# Dashboard_Test_External_rev0.net
KiCad netlist of a schematic drawn in EAGLE
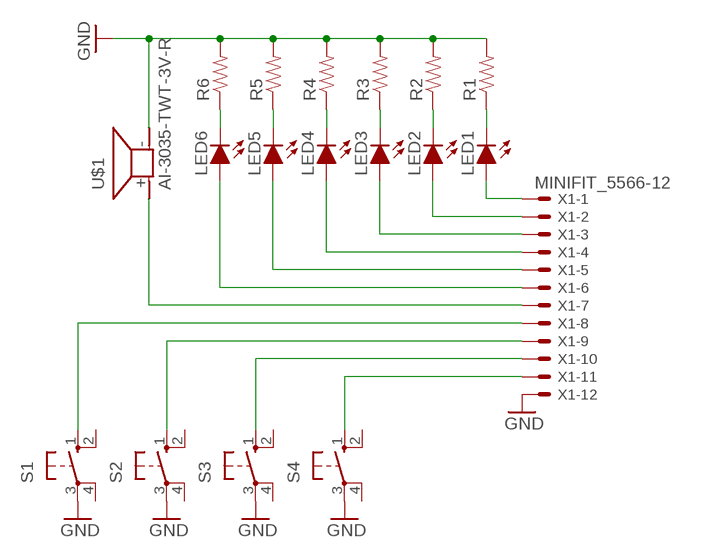
[diagram p0: schematic, sheet 1]

(export (version "E")
  (design (tool "Eeschema 10.0.6"))
  (components
    (comp (ref "LED1")
      (value "LED-5MM")
      (footprint "eagle-import:LED-5MM")
      (libsource (lib "eagle-import") (part "LED-5MM"))
    )
    (comp (ref "LED2")
      (value "LED-5MM")
      (footprint "eagle-import:LED-5MM")
      (libsource (lib "eagle-import") (part "LED-5MM"))
    )
    (comp (ref "LED3")
      (value "LED-5MM")
      (footprint "eagle-import:LED-5MM")
      (libsource (lib "eagle-import") (part "LED-5MM"))
    )
    (comp (ref "LED4")
      (value "LED-5MM")
      (footprint "eagle-import:LED-5MM")
      (libsource (lib "eagle-import") (part "LED-5MM"))
    )
    (comp (ref "LED5")
      (value "LED-5MM")
      (footprint "eagle-import:LED-5MM")
      (libsource (lib "eagle-import") (part "LED-5MM"))
    )
    (comp (ref "LED6")
      (value "LED-5MM")
      (footprint "eagle-import:LED-5MM")
      (libsource (lib "eagle-import") (part "LED-5MM"))
    )
    (comp (ref "R1")
      (value "RESISTOREZ")
      (footprint "eagle-import:AXIAL-0.3EZ")
      (libsource (lib "eagle-import") (part "RESISTOREZ"))
    )
    (comp (ref "R2")
      (value "RESISTOREZ")
      (footprint "eagle-import:AXIAL-0.3EZ")
      (libsource (lib "eagle-import") (part "RESISTOREZ"))
    )
    (comp (ref "R3")
      (value "RESISTOREZ")
      (footprint "eagle-import:AXIAL-0.3EZ")
      (libsource (lib "eagle-import") (part "RESISTOREZ"))
    )
    (comp (ref "R4")
      (value "RESISTOREZ")
      (footprint "eagle-import:AXIAL-0.3EZ")
      (libsource (lib "eagle-import") (part "RESISTOREZ"))
    )
    (comp (ref "R5")
      (value "RESISTOREZ")
      (footprint "eagle-import:AXIAL-0.3EZ")
      (libsource (lib "eagle-import") (part "RESISTOREZ"))
    )
    (comp (ref "R6")
      (value "RESISTOREZ")
      (footprint "eagle-import:AXIAL-0.3EZ")
      (libsource (lib "eagle-import") (part "RESISTOREZ"))
    )
    (comp (ref "S1")
      (value "BTN_10-XX")
      (footprint "eagle-import:B3F-10XX")
      (fields (field (name "MPN") "B3F-1000"))
      (libsource (lib "eagle-import") (part "BTN_10-XX"))
    )
    (comp (ref "S2")
      (value "BTN_10-XX")
      (footprint "eagle-import:B3F-10XX")
      (fields (field (name "MPN") "B3F-1000"))
      (libsource (lib "eagle-import") (part "BTN_10-XX"))
    )
    (comp (ref "S3")
      (value "BTN_10-XX")
      (footprint "eagle-import:B3F-10XX")
      (fields (field (name "MPN") "B3F-1000"))
      (libsource (lib "eagle-import") (part "BTN_10-XX"))
    )
    (comp (ref "S4")
      (value "BTN_10-XX")
      (footprint "eagle-import:B3F-10XX")
      (fields (field (name "MPN") "B3F-1000"))
      (libsource (lib "eagle-import") (part "BTN_10-XX"))
    )
    (comp (ref "U$1")
      (value "AI-3035-TWT-3V-R")
      (footprint "eagle-import:AI-3035-TWT-3V-R")
      (libsource (lib "eagle-import") (part "AI-3035-TWT-3V-R"))
    )
    (comp (ref "X1")
      (value "MINIFIT_5566-12")
      (footprint "eagle-import:MINIFIT_5566-12")
      (libsource (lib "eagle-import") (part "MINIFIT_5566-12"))
    )
  )
  (nets
    (net (code "1") (name "GND") (class "Default")
      (node (ref "R1") (pin "P$2") (pinfunction "2_P$2") (pintype "passive"))
      (node (ref "R2") (pin "P$2") (pinfunction "2_P$2") (pintype "passive"))
      (node (ref "R3") (pin "P$2") (pinfunction "2_P$2") (pintype "passive"))
      (node (ref "R4") (pin "P$2") (pinfunction "2_P$2") (pintype "passive"))
      (node (ref "R5") (pin "P$2") (pinfunction "2_P$2") (pintype "passive"))
      (node (ref "R6") (pin "P$2") (pinfunction "2_P$2") (pintype "passive"))
      (node (ref "S1") (pin "3") (pinfunction "P_3") (pintype "passive"))
      (node (ref "S2") (pin "3") (pinfunction "P_3") (pintype "passive"))
      (node (ref "S3") (pin "3") (pinfunction "P_3") (pintype "passive"))
      (node (ref "S4") (pin "3") (pinfunction "P_3") (pintype "passive"))
      (node (ref "U$1") (pin "P$2") (pinfunction "2_P$2") (pintype "passive"))
      (node (ref "X1") (pin "12") (pinfunction "S_12") (pintype "passive"))
    )
    (net (code "2") (name "Net-(LED1-C)") (class "Default")
      (node (ref "LED1") (pin "K") (pinfunction "C_K") (pintype "passive"))
      (node (ref "R1") (pin "P$1") (pinfunction "1_P$1") (pintype "passive"))
    )
    (net (code "3") (name "Net-(LED2-C)") (class "Default")
      (node (ref "LED2") (pin "K") (pinfunction "C_K") (pintype "passive"))
      (node (ref "R2") (pin "P$1") (pinfunction "1_P$1") (pintype "passive"))
    )
    (net (code "4") (name "Net-(LED3-C)") (class "Default")
      (node (ref "LED3") (pin "K") (pinfunction "C_K") (pintype "passive"))
      (node (ref "R3") (pin "P$1") (pinfunction "1_P$1") (pintype "passive"))
    )
    (net (code "5") (name "Net-(LED4-C)") (class "Default")
      (node (ref "LED4") (pin "K") (pinfunction "C_K") (pintype "passive"))
      (node (ref "R4") (pin "P$1") (pinfunction "1_P$1") (pintype "passive"))
    )
    (net (code "6") (name "Net-(LED5-C)") (class "Default")
      (node (ref "LED5") (pin "K") (pinfunction "C_K") (pintype "passive"))
      (node (ref "R5") (pin "P$1") (pinfunction "1_P$1") (pintype "passive"))
    )
    (net (code "7") (name "Net-(LED6-C)") (class "Default")
      (node (ref "LED6") (pin "K") (pinfunction "C_K") (pintype "passive"))
      (node (ref "R6") (pin "P$1") (pinfunction "1_P$1") (pintype "passive"))
    )
    (net (code "8") (name "Net-(S1-S)") (class "Default")
      (node (ref "S1") (pin "1") (pinfunction "S_1") (pintype "passive"))
      (node (ref "X1") (pin "8") (pinfunction "S_8") (pintype "passive"))
    )
    (net (code "9") (name "Net-(S2-S)") (class "Default")
      (node (ref "S2") (pin "1") (pinfunction "S_1") (pintype "passive"))
      (node (ref "X1") (pin "9") (pinfunction "S_9") (pintype "passive"))
    )
    (net (code "10") (name "Net-(S3-S)") (class "Default")
      (node (ref "S3") (pin "1") (pinfunction "S_1") (pintype "passive"))
      (node (ref "X1") (pin "10") (pinfunction "S_10") (pintype "passive"))
    )
    (net (code "11") (name "Net-(S4-S)") (class "Default")
      (node (ref "S4") (pin "1") (pinfunction "S_1") (pintype "passive"))
      (node (ref "X1") (pin "11") (pinfunction "S_11") (pintype "passive"))
    )
    (net (code "12") (name "Net-(U$1-1)") (class "Default")
      (node (ref "U$1") (pin "P$1") (pinfunction "1_P$1") (pintype "passive"))
      (node (ref "X1") (pin "7") (pinfunction "S_7") (pintype "passive"))
    )
    (net (code "13") (name "Net-(X1A-S)") (class "Default")
      (node (ref "LED1") (pin "A") (pinfunction "A_A") (pintype "passive"))
      (node (ref "X1") (pin "1") (pinfunction "S_1") (pintype "passive"))
    )
    (net (code "14") (name "Net-(X1E-S)") (class "Default")
      (node (ref "LED2") (pin "A") (pinfunction "A_A") (pintype "passive"))
      (node (ref "X1") (pin "2") (pinfunction "S_2") (pintype "passive"))
    )
    (net (code "15") (name "Net-(X1F-S)") (class "Default")
      (node (ref "LED3") (pin "A") (pinfunction "A_A") (pintype "passive"))
      (node (ref "X1") (pin "3") (pinfunction "S_3") (pintype "passive"))
    )
    (net (code "16") (name "Net-(X1G-S)") (class "Default")
      (node (ref "LED4") (pin "A") (pinfunction "A_A") (pintype "passive"))
      (node (ref "X1") (pin "4") (pinfunction "S_4") (pintype "passive"))
    )
    (net (code "17") (name "Net-(X1H-S)") (class "Default")
      (node (ref "LED5") (pin "A") (pinfunction "A_A") (pintype "passive"))
      (node (ref "X1") (pin "5") (pinfunction "S_5") (pintype "passive"))
    )
    (net (code "18") (name "Net-(X1I-S)") (class "Default")
      (node (ref "LED6") (pin "A") (pinfunction "A_A") (pintype "passive"))
      (node (ref "X1") (pin "6") (pinfunction "S_6") (pintype "passive"))
    )
    (net (code "19") (name "unconnected-(S1-P1-Pad4)") (class "Default")
      (node (ref "S1") (pin "4") (pinfunction "P1_4") (pintype "passive"))
    )
    (net (code "20") (name "unconnected-(S1-S1-Pad2)") (class "Default")
      (node (ref "S1") (pin "2") (pinfunction "S1_2") (pintype "passive"))
    )
    (net (code "21") (name "unconnected-(S2-P1-Pad4)") (class "Default")
      (node (ref "S2") (pin "4") (pinfunction "P1_4") (pintype "passive"))
    )
    (net (code "22") (name "unconnected-(S2-S1-Pad2)") (class "Default")
      (node (ref "S2") (pin "2") (pinfunction "S1_2") (pintype "passive"))
    )
    (net (code "23") (name "unconnected-(S3-P1-Pad4)") (class "Default")
      (node (ref "S3") (pin "4") (pinfunction "P1_4") (pintype "passive"))
    )
    (net (code "24") (name "unconnected-(S3-S1-Pad2)") (class "Default")
      (node (ref "S3") (pin "2") (pinfunction "S1_2") (pintype "passive"))
    )
    (net (code "25") (name "unconnected-(S4-P1-Pad4)") (class "Default")
      (node (ref "S4") (pin "4") (pinfunction "P1_4") (pintype "passive"))
    )
    (net (code "26") (name "unconnected-(S4-S1-Pad2)") (class "Default")
      (node (ref "S4") (pin "2") (pinfunction "S1_2") (pintype "passive"))
    )
  )
)
